# V0_2.net
KiCad netlist of a schematic drawn in EAGLE
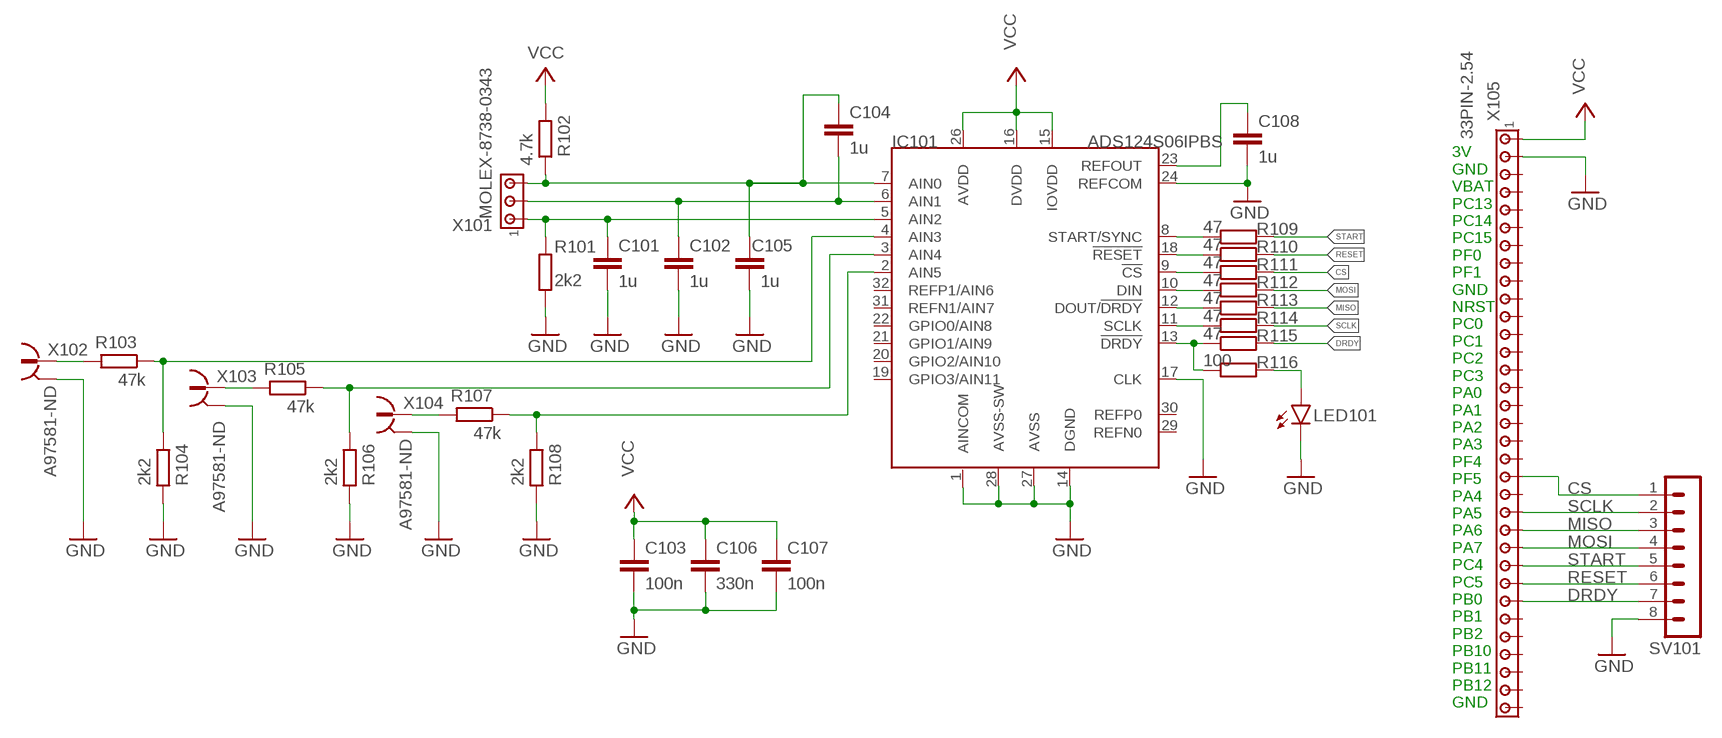
[diagram p0: schematic, sheet 1]

(export (version "E")
  (design (tool "Eeschema 10.0.6"))
  (components
    (comp (ref "C101")
      (value "1u")
      (footprint "eagle-import:C0603")
      (libsource (lib "eagle-import") (part "C-EUC0603"))
    )
    (comp (ref "C102")
      (value "1u")
      (footprint "eagle-import:C0603")
      (libsource (lib "eagle-import") (part "C-EUC0603"))
    )
    (comp (ref "C103")
      (value "100n")
      (footprint "eagle-import:C0603")
      (libsource (lib "eagle-import") (part "C-EUC0603"))
    )
    (comp (ref "C104")
      (value "1u")
      (footprint "eagle-import:C0603")
      (libsource (lib "eagle-import") (part "C-EUC0603"))
    )
    (comp (ref "C105")
      (value "1u")
      (footprint "eagle-import:C0603")
      (libsource (lib "eagle-import") (part "C-EUC0603"))
    )
    (comp (ref "C106")
      (value "330n")
      (footprint "eagle-import:C0603")
      (libsource (lib "eagle-import") (part "C-EUC0603"))
    )
    (comp (ref "C107")
      (value "100n")
      (footprint "eagle-import:C0603")
      (libsource (lib "eagle-import") (part "C-EUC0603"))
    )
    (comp (ref "C108")
      (value "1u")
      (footprint "eagle-import:C0603")
      (libsource (lib "eagle-import") (part "C-EUC0603"))
    )
    (comp (ref "IC101")
      (value "ADS124S06IPBS")
      (footprint "eagle-import:TQFP32-05")
      (libsource (lib "eagle-import") (part "ADS124S0XIPBS"))
    )
    (comp (ref "LED101")
      (value "LEDSML0603")
      (footprint "eagle-import:SML0603")
      (libsource (lib "eagle-import") (part "LEDSML0603"))
    )
    (comp (ref "R101")
      (value "2k2")
      (footprint "eagle-import:R0805W")
      (libsource (lib "eagle-import") (part "R-EU_R0805W"))
    )
    (comp (ref "R102")
      (value "4.7k")
      (footprint "eagle-import:R0603")
      (libsource (lib "eagle-import") (part "R-EU_R0603"))
    )
    (comp (ref "R103")
      (value "47k")
      (footprint "eagle-import:R0603")
      (libsource (lib "eagle-import") (part "R-EU_R0603"))
    )
    (comp (ref "R104")
      (value "2k2")
      (footprint "eagle-import:R0805W")
      (libsource (lib "eagle-import") (part "R-EU_R0805W"))
    )
    (comp (ref "R105")
      (value "47k")
      (footprint "eagle-import:R0603")
      (libsource (lib "eagle-import") (part "R-EU_R0603"))
    )
    (comp (ref "R106")
      (value "2k2")
      (footprint "eagle-import:R0805W")
      (libsource (lib "eagle-import") (part "R-EU_R0805W"))
    )
    (comp (ref "R107")
      (value "47k")
      (footprint "eagle-import:R0603")
      (libsource (lib "eagle-import") (part "R-EU_R0603"))
    )
    (comp (ref "R108")
      (value "2k2")
      (footprint "eagle-import:R0805W")
      (libsource (lib "eagle-import") (part "R-EU_R0805W"))
    )
    (comp (ref "R109")
      (value "47")
      (footprint "eagle-import:R0603")
      (libsource (lib "eagle-import") (part "R-EU_R0603"))
    )
    (comp (ref "R110")
      (value "47")
      (footprint "eagle-import:R0603")
      (libsource (lib "eagle-import") (part "R-EU_R0603"))
    )
    (comp (ref "R111")
      (value "47")
      (footprint "eagle-import:R0603")
      (libsource (lib "eagle-import") (part "R-EU_R0603"))
    )
    (comp (ref "R112")
      (value "47")
      (footprint "eagle-import:R0603")
      (libsource (lib "eagle-import") (part "R-EU_R0603"))
    )
    (comp (ref "R113")
      (value "47")
      (footprint "eagle-import:R0603")
      (libsource (lib "eagle-import") (part "R-EU_R0603"))
    )
    (comp (ref "R114")
      (value "47")
      (footprint "eagle-import:R0603")
      (libsource (lib "eagle-import") (part "R-EU_R0603"))
    )
    (comp (ref "R115")
      (value "47")
      (footprint "eagle-import:R0603")
      (libsource (lib "eagle-import") (part "R-EU_R0603"))
    )
    (comp (ref "R116")
      (value "100")
      (footprint "eagle-import:R0603")
      (libsource (lib "eagle-import") (part "R-EU_R0603"))
    )
    (comp (ref "SV101")
      (value "MA08-1")
      (footprint "eagle-import:MA08-1")
      (libsource (lib "eagle-import") (part "MA08-1"))
    )
    (comp (ref "X101")
      (value "MOLEX-8738-0343")
      (footprint "eagle-import:MOLEX-87438-0343")
      (libsource (lib "eagle-import") (part "MOLEX-8738-0343"))
    )
    (comp (ref "X102")
      (value "A97581-ND")
      (footprint "eagle-import:1634503")
      (libsource (lib "eagle-import") (part "A97581-ND"))
    )
    (comp (ref "X103")
      (value "A97581-ND")
      (footprint "eagle-import:1634503")
      (libsource (lib "eagle-import") (part "A97581-ND"))
    )
    (comp (ref "X104")
      (value "A97581-ND")
      (footprint "eagle-import:1634503")
      (libsource (lib "eagle-import") (part "A97581-ND"))
    )
    (comp (ref "X105")
      (value "33PIN-2.54")
      (footprint "eagle-import:1X33")
      (libsource (lib "eagle-import") (part "33PIN-2.54"))
    )
  )
  (nets
    (net (code "1") (name "CS") (class "Default")
      (node (ref "R111") (pin "2") (pinfunction "2_2") (pintype "passive"))
      (node (ref "SV101") (pin "1") (pinfunction "1_1") (pintype "passive"))
      (node (ref "X105") (pin "20") (pinfunction "20_20") (pintype "passive"))
    )
    (net (code "2") (name "DRDY") (class "Default")
      (node (ref "R115") (pin "2") (pinfunction "2_2") (pintype "passive"))
      (node (ref "SV101") (pin "7") (pinfunction "7_7") (pintype "passive"))
      (node (ref "X105") (pin "27") (pinfunction "27_27") (pintype "passive"))
    )
    (net (code "3") (name "GND") (class "Default")
      (node (ref "C101") (pin "2") (pinfunction "2_2") (pintype "passive"))
      (node (ref "C102") (pin "2") (pinfunction "2_2") (pintype "passive"))
      (node (ref "C103") (pin "2") (pinfunction "2_2") (pintype "passive"))
      (node (ref "C105") (pin "2") (pinfunction "2_2") (pintype "passive"))
      (node (ref "C106") (pin "2") (pinfunction "2_2") (pintype "passive"))
      (node (ref "C107") (pin "2") (pinfunction "2_2") (pintype "passive"))
      (node (ref "C108") (pin "2") (pinfunction "2_2") (pintype "passive"))
      (node (ref "IC101") (pin "1") (pinfunction "AINCOM_1") (pintype "bidirectional"))
      (node (ref "IC101") (pin "14") (pinfunction "DGND_14") (pintype "bidirectional"))
      (node (ref "IC101") (pin "17") (pinfunction "CLK_17") (pintype "bidirectional"))
      (node (ref "IC101") (pin "24") (pinfunction "REFCOM_24") (pintype "bidirectional"))
      (node (ref "IC101") (pin "27") (pinfunction "AVSS_27") (pintype "bidirectional"))
      (node (ref "IC101") (pin "28") (pinfunction "AVSS-SW_28") (pintype "bidirectional"))
      (node (ref "LED101") (pin "C") (pinfunction "C_C") (pintype "passive"))
      (node (ref "R101") (pin "1") (pinfunction "1_1") (pintype "passive"))
      (node (ref "R104") (pin "1") (pinfunction "1_1") (pintype "passive"))
      (node (ref "R106") (pin "1") (pinfunction "1_1") (pintype "passive"))
      (node (ref "R108") (pin "1") (pinfunction "1_1") (pintype "passive"))
      (node (ref "SV101") (pin "8") (pinfunction "8_8") (pintype "passive"))
      (node (ref "X102") (pin "2") (pinfunction "2_2") (pintype "passive"))
      (node (ref "X102") (pin "3") (pinfunction "2_3") (pintype "passive"))
      (node (ref "X102") (pin "4") (pinfunction "2_4") (pintype "passive"))
      (node (ref "X102") (pin "5") (pinfunction "2_5") (pintype "passive"))
      (node (ref "X103") (pin "2") (pinfunction "2_2") (pintype "passive"))
      (node (ref "X103") (pin "3") (pinfunction "2_3") (pintype "passive"))
      (node (ref "X103") (pin "4") (pinfunction "2_4") (pintype "passive"))
      (node (ref "X103") (pin "5") (pinfunction "2_5") (pintype "passive"))
      (node (ref "X104") (pin "2") (pinfunction "2_2") (pintype "passive"))
      (node (ref "X104") (pin "3") (pinfunction "2_3") (pintype "passive"))
      (node (ref "X104") (pin "4") (pinfunction "2_4") (pintype "passive"))
      (node (ref "X104") (pin "5") (pinfunction "2_5") (pintype "passive"))
      (node (ref "X105") (pin "2") (pinfunction "2_2") (pintype "passive"))
    )
    (net (code "4") (name "MISO") (class "Default")
      (node (ref "R113") (pin "2") (pinfunction "2_2") (pintype "passive"))
      (node (ref "SV101") (pin "3") (pinfunction "3_3") (pintype "passive"))
      (node (ref "X105") (pin "23") (pinfunction "23_23") (pintype "passive"))
    )
    (net (code "5") (name "MOSI") (class "Default")
      (node (ref "R112") (pin "2") (pinfunction "2_2") (pintype "passive"))
      (node (ref "SV101") (pin "4") (pinfunction "4_4") (pintype "passive"))
      (node (ref "X105") (pin "24") (pinfunction "24_24") (pintype "passive"))
    )
    (net (code "6") (name "Net-(IC101-AIN0)") (class "Default")
      (node (ref "C104") (pin "1") (pinfunction "1_1") (pintype "passive"))
      (node (ref "C105") (pin "1") (pinfunction "1_1") (pintype "passive"))
      (node (ref "IC101") (pin "7") (pinfunction "AIN0_7") (pintype "bidirectional"))
      (node (ref "R102") (pin "1") (pinfunction "1_1") (pintype "passive"))
      (node (ref "X101") (pin "3") (pinfunction "3_3") (pintype "passive"))
      (node (ref "X101") (pin "3_1") (pinfunction "3_3_1") (pintype "passive"))
    )
    (net (code "7") (name "Net-(IC101-AIN1)") (class "Default")
      (node (ref "C102") (pin "1") (pinfunction "1_1") (pintype "passive"))
      (node (ref "C104") (pin "2") (pinfunction "2_2") (pintype "passive"))
      (node (ref "IC101") (pin "6") (pinfunction "AIN1_6") (pintype "bidirectional"))
      (node (ref "X101") (pin "2") (pinfunction "2_2") (pintype "passive"))
      (node (ref "X101") (pin "2_1") (pinfunction "2_2_1") (pintype "passive"))
    )
    (net (code "8") (name "Net-(IC101-AIN2)") (class "Default")
      (node (ref "C101") (pin "1") (pinfunction "1_1") (pintype "passive"))
      (node (ref "IC101") (pin "5") (pinfunction "AIN2_5") (pintype "bidirectional"))
      (node (ref "R101") (pin "2") (pinfunction "2_2") (pintype "passive"))
      (node (ref "X101") (pin "1") (pinfunction "1_1") (pintype "passive"))
      (node (ref "X101") (pin "1_1") (pinfunction "1_1_1") (pintype "passive"))
    )
    (net (code "9") (name "Net-(IC101-AIN3)") (class "Default")
      (node (ref "IC101") (pin "4") (pinfunction "AIN3_4") (pintype "bidirectional"))
      (node (ref "R103") (pin "1") (pinfunction "1_1") (pintype "passive"))
      (node (ref "R104") (pin "2") (pinfunction "2_2") (pintype "passive"))
    )
    (net (code "10") (name "Net-(IC101-AIN4)") (class "Default")
      (node (ref "IC101") (pin "3") (pinfunction "AIN4_3") (pintype "bidirectional"))
      (node (ref "R105") (pin "1") (pinfunction "1_1") (pintype "passive"))
      (node (ref "R106") (pin "2") (pinfunction "2_2") (pintype "passive"))
    )
    (net (code "11") (name "Net-(IC101-AIN5)") (class "Default")
      (node (ref "IC101") (pin "2") (pinfunction "AIN5_2") (pintype "bidirectional"))
      (node (ref "R107") (pin "1") (pinfunction "1_1") (pintype "passive"))
      (node (ref "R108") (pin "2") (pinfunction "2_2") (pintype "passive"))
    )
    (net (code "12") (name "Net-(IC101-DIN)") (class "Default")
      (node (ref "IC101") (pin "10") (pinfunction "DIN_10") (pintype "bidirectional"))
      (node (ref "R112") (pin "1") (pinfunction "1_1") (pintype "passive"))
    )
    (net (code "13") (name "Net-(IC101-DOUT{slash}~{DRDY})") (class "Default")
      (node (ref "IC101") (pin "12") (pinfunction "DOUT/~{DRDY}_12") (pintype "bidirectional"))
      (node (ref "R113") (pin "1") (pinfunction "1_1") (pintype "passive"))
    )
    (net (code "14") (name "Net-(IC101-REFOUT)") (class "Default")
      (node (ref "C108") (pin "1") (pinfunction "1_1") (pintype "passive"))
      (node (ref "IC101") (pin "23") (pinfunction "REFOUT_23") (pintype "bidirectional"))
    )
    (net (code "15") (name "Net-(IC101-SCLK)") (class "Default")
      (node (ref "IC101") (pin "11") (pinfunction "SCLK_11") (pintype "bidirectional"))
      (node (ref "R114") (pin "1") (pinfunction "1_1") (pintype "passive"))
    )
    (net (code "16") (name "Net-(IC101-START{slash}SYNC)") (class "Default")
      (node (ref "IC101") (pin "8") (pinfunction "START/SYNC_8") (pintype "bidirectional"))
      (node (ref "R109") (pin "1") (pinfunction "1_1") (pintype "passive"))
    )
    (net (code "17") (name "Net-(IC101-~{CS})") (class "Default")
      (node (ref "IC101") (pin "9") (pinfunction "~{CS}_9") (pintype "bidirectional"))
      (node (ref "R111") (pin "1") (pinfunction "1_1") (pintype "passive"))
    )
    (net (code "18") (name "Net-(IC101-~{DRDY})") (class "Default")
      (node (ref "IC101") (pin "13") (pinfunction "~{DRDY}_13") (pintype "bidirectional"))
      (node (ref "R115") (pin "1") (pinfunction "1_1") (pintype "passive"))
      (node (ref "R116") (pin "1") (pinfunction "1_1") (pintype "passive"))
    )
    (net (code "19") (name "Net-(IC101-~{RESET})") (class "Default")
      (node (ref "IC101") (pin "18") (pinfunction "~{RESET}_18") (pintype "bidirectional"))
      (node (ref "R110") (pin "1") (pinfunction "1_1") (pintype "passive"))
    )
    (net (code "20") (name "Net-(LED101-PadA)") (class "Default")
      (node (ref "LED101") (pin "A") (pinfunction "A_A") (pintype "passive"))
      (node (ref "R116") (pin "2") (pinfunction "2_2") (pintype "passive"))
    )
    (net (code "21") (name "Net-(R103-Pad2)") (class "Default")
      (node (ref "R103") (pin "2") (pinfunction "2_2") (pintype "passive"))
      (node (ref "X102") (pin "1") (pinfunction "1_1") (pintype "passive"))
    )
    (net (code "22") (name "Net-(R105-Pad2)") (class "Default")
      (node (ref "R105") (pin "2") (pinfunction "2_2") (pintype "passive"))
      (node (ref "X103") (pin "1") (pinfunction "1_1") (pintype "passive"))
    )
    (net (code "23") (name "Net-(R107-Pad2)") (class "Default")
      (node (ref "R107") (pin "2") (pinfunction "2_2") (pintype "passive"))
      (node (ref "X104") (pin "1") (pinfunction "1_1") (pintype "passive"))
    )
    (net (code "24") (name "RESET") (class "Default")
      (node (ref "R110") (pin "2") (pinfunction "2_2") (pintype "passive"))
      (node (ref "SV101") (pin "6") (pinfunction "6_6") (pintype "passive"))
      (node (ref "X105") (pin "26") (pinfunction "26_26") (pintype "passive"))
    )
    (net (code "25") (name "SCLK") (class "Default")
      (node (ref "R114") (pin "2") (pinfunction "2_2") (pintype "passive"))
      (node (ref "SV101") (pin "2") (pinfunction "2_2") (pintype "passive"))
      (node (ref "X105") (pin "22") (pinfunction "22_22") (pintype "passive"))
    )
    (net (code "26") (name "START") (class "Default")
      (node (ref "R109") (pin "2") (pinfunction "2_2") (pintype "passive"))
      (node (ref "SV101") (pin "5") (pinfunction "5_5") (pintype "passive"))
      (node (ref "X105") (pin "25") (pinfunction "25_25") (pintype "passive"))
    )
    (net (code "27") (name "VCC") (class "Default")
      (node (ref "C103") (pin "1") (pinfunction "1_1") (pintype "passive"))
      (node (ref "C106") (pin "1") (pinfunction "1_1") (pintype "passive"))
      (node (ref "C107") (pin "1") (pinfunction "1_1") (pintype "passive"))
      (node (ref "IC101") (pin "15") (pinfunction "IOVDD_15") (pintype "bidirectional"))
      (node (ref "IC101") (pin "16") (pinfunction "DVDD_16") (pintype "bidirectional"))
      (node (ref "IC101") (pin "26") (pinfunction "AVDD_26") (pintype "bidirectional"))
      (node (ref "R102") (pin "2") (pinfunction "2_2") (pintype "passive"))
      (node (ref "X105") (pin "1") (pinfunction "1_1") (pintype "passive"))
    )
    (net (code "28") (name "unconnected-(IC101-GPIO0{slash}AIN8-Pad22)") (class "Default")
      (node (ref "IC101") (pin "22") (pinfunction "GPIO0/AIN8_22") (pintype "bidirectional"))
    )
    (net (code "29") (name "unconnected-(IC101-GPIO1{slash}AIN9-Pad21)") (class "Default")
      (node (ref "IC101") (pin "21") (pinfunction "GPIO1/AIN9_21") (pintype "bidirectional"))
    )
    (net (code "30") (name "unconnected-(IC101-GPIO2{slash}AIN10-Pad20)") (class "Default")
      (node (ref "IC101") (pin "20") (pinfunction "GPIO2/AIN10_20") (pintype "bidirectional"))
    )
    (net (code "31") (name "unconnected-(IC101-GPIO3{slash}AIN11-Pad19)") (class "Default")
      (node (ref "IC101") (pin "19") (pinfunction "GPIO3/AIN11_19") (pintype "bidirectional"))
    )
    (net (code "32") (name "unconnected-(IC101-REFN0-Pad29)") (class "Default")
      (node (ref "IC101") (pin "29") (pinfunction "REFN0_29") (pintype "bidirectional"))
    )
    (net (code "33") (name "unconnected-(IC101-REFN1{slash}AIN7-Pad31)") (class "Default")
      (node (ref "IC101") (pin "31") (pinfunction "REFN1/AIN7_31") (pintype "bidirectional"))
    )
    (net (code "34") (name "unconnected-(IC101-REFP0-Pad30)") (class "Default")
      (node (ref "IC101") (pin "30") (pinfunction "REFP0_30") (pintype "bidirectional"))
    )
    (net (code "35") (name "unconnected-(IC101-REFP1{slash}AIN6-Pad32)") (class "Default")
      (node (ref "IC101") (pin "32") (pinfunction "REFP1/AIN6_32") (pintype "bidirectional"))
    )
    (net (code "36") (name "unconnected-(X105-Pad3)") (class "Default")
      (node (ref "X105") (pin "3") (pinfunction "3_3") (pintype "passive"))
    )
    (net (code "37") (name "unconnected-(X105-Pad4)") (class "Default")
      (node (ref "X105") (pin "4") (pinfunction "4_4") (pintype "passive"))
    )
    (net (code "38") (name "unconnected-(X105-Pad5)") (class "Default")
      (node (ref "X105") (pin "5") (pinfunction "5_5") (pintype "passive"))
    )
    (net (code "39") (name "unconnected-(X105-Pad6)") (class "Default")
      (node (ref "X105") (pin "6") (pinfunction "6_6") (pintype "passive"))
    )
    (net (code "40") (name "unconnected-(X105-Pad7)") (class "Default")
      (node (ref "X105") (pin "7") (pinfunction "7_7") (pintype "passive"))
    )
    (net (code "41") (name "unconnected-(X105-Pad8)") (class "Default")
      (node (ref "X105") (pin "8") (pinfunction "8_8") (pintype "passive"))
    )
    (net (code "42") (name "unconnected-(X105-Pad9)") (class "Default")
      (node (ref "X105") (pin "9") (pinfunction "9_9") (pintype "passive"))
    )
    (net (code "43") (name "unconnected-(X105-Pad10)") (class "Default")
      (node (ref "X105") (pin "10") (pinfunction "10_10") (pintype "passive"))
    )
    (net (code "44") (name "unconnected-(X105-Pad11)") (class "Default")
      (node (ref "X105") (pin "11") (pinfunction "11_11") (pintype "passive"))
    )
    (net (code "45") (name "unconnected-(X105-Pad12)") (class "Default")
      (node (ref "X105") (pin "12") (pinfunction "12_12") (pintype "passive"))
    )
    (net (code "46") (name "unconnected-(X105-Pad13)") (class "Default")
      (node (ref "X105") (pin "13") (pinfunction "13_13") (pintype "passive"))
    )
    (net (code "47") (name "unconnected-(X105-Pad14)") (class "Default")
      (node (ref "X105") (pin "14") (pinfunction "14_14") (pintype "passive"))
    )
    (net (code "48") (name "unconnected-(X105-Pad15)") (class "Default")
      (node (ref "X105") (pin "15") (pinfunction "15_15") (pintype "passive"))
    )
    (net (code "49") (name "unconnected-(X105-Pad16)") (class "Default")
      (node (ref "X105") (pin "16") (pinfunction "16_16") (pintype "passive"))
    )
    (net (code "50") (name "unconnected-(X105-Pad17)") (class "Default")
      (node (ref "X105") (pin "17") (pinfunction "17_17") (pintype "passive"))
    )
    (net (code "51") (name "unconnected-(X105-Pad18)") (class "Default")
      (node (ref "X105") (pin "18") (pinfunction "18_18") (pintype "passive"))
    )
    (net (code "52") (name "unconnected-(X105-Pad19)") (class "Default")
      (node (ref "X105") (pin "19") (pinfunction "19_19") (pintype "passive"))
    )
    (net (code "53") (name "unconnected-(X105-Pad21)") (class "Default")
      (node (ref "X105") (pin "21") (pinfunction "21_21") (pintype "passive"))
    )
    (net (code "54") (name "unconnected-(X105-Pad28)") (class "Default")
      (node (ref "X105") (pin "28") (pinfunction "28_28") (pintype "passive"))
    )
    (net (code "55") (name "unconnected-(X105-Pad29)") (class "Default")
      (node (ref "X105") (pin "29") (pinfunction "29_29") (pintype "passive"))
    )
    (net (code "56") (name "unconnected-(X105-Pad30)") (class "Default")
      (node (ref "X105") (pin "30") (pinfunction "30_30") (pintype "passive"))
    )
    (net (code "57") (name "unconnected-(X105-Pad31)") (class "Default")
      (node (ref "X105") (pin "31") (pinfunction "31_31") (pintype "passive"))
    )
    (net (code "58") (name "unconnected-(X105-Pad32)") (class "Default")
      (node (ref "X105") (pin "32") (pinfunction "32_32") (pintype "passive"))
    )
    (net (code "59") (name "unconnected-(X105-Pad33)") (class "Default")
      (node (ref "X105") (pin "33") (pinfunction "33_33") (pintype "passive"))
    )
  )
)
